# lv_io_retro.net
KiCad netlist of a schematic drawn in Altium Designer
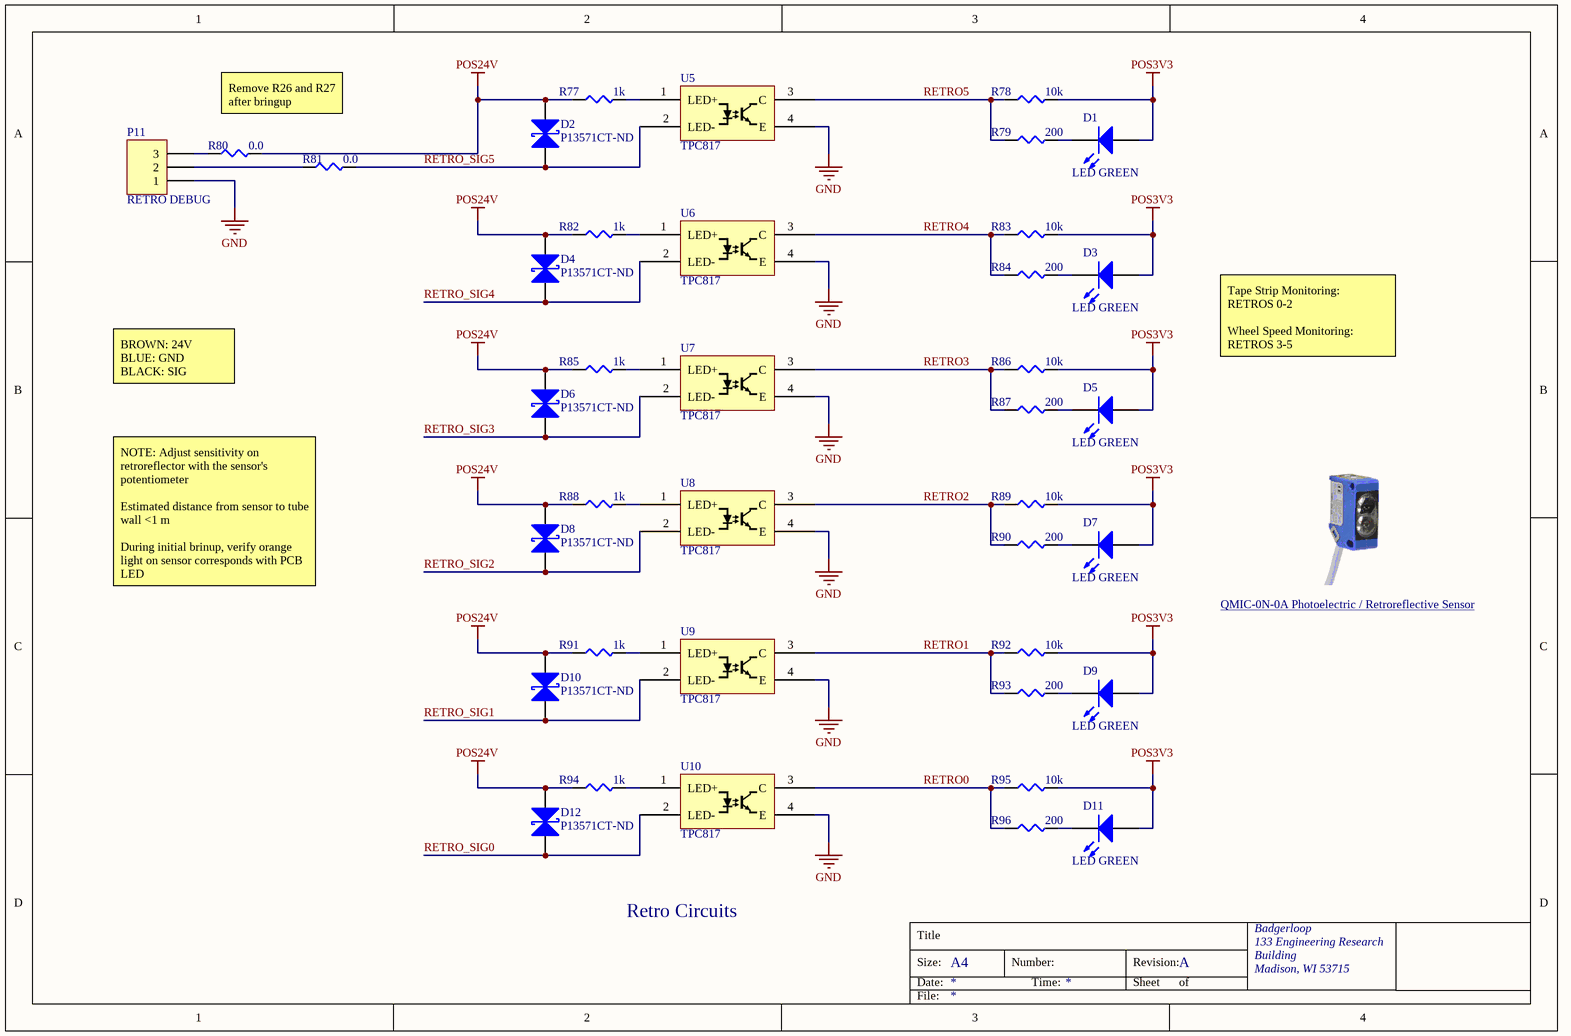
[diagram p0: lv_io_retro.SchDoc]

(export (version "E")
  (design (tool "Eeschema 10.0.6"))
  (components
    (comp (ref "D1")
      (value "LED GREEN")
      (footprint "LED 0603 GREEN")
      (fields (field (name "MANUFACTURER") "Lite-On Inc."))
      (libsource (lib "misc") (part "LED GREEN 0603"))
    )
    (comp (ref "D2")
      (value "ESD Diode")
      (footprint "SMD-0402-RES")
      (description "ESD Supressor")
      (fields (field (name "DIGIKEY P/N") "P13571CT-ND") (field (name "MANUFACTURER") "EZAEG"))
      (libsource (lib "misc") (part "ESD Diode"))
    )
    (comp (ref "D3")
      (value "LED GREEN")
      (footprint "LED 0603 GREEN")
      (fields (field (name "MANUFACTURER") "Lite-On Inc."))
      (libsource (lib "misc") (part "LED GREEN 0603"))
    )
    (comp (ref "D4")
      (value "ESD Diode")
      (footprint "SMD-0402-RES")
      (description "ESD Supressor")
      (fields (field (name "DIGIKEY P/N") "P13571CT-ND") (field (name "MANUFACTURER") "EZAEG"))
      (libsource (lib "misc") (part "ESD Diode"))
    )
    (comp (ref "D5")
      (value "LED GREEN")
      (footprint "LED 0603 GREEN")
      (fields (field (name "MANUFACTURER") "Lite-On Inc."))
      (libsource (lib "misc") (part "LED GREEN 0603"))
    )
    (comp (ref "D6")
      (value "ESD Diode")
      (footprint "SMD-0402-RES")
      (description "ESD Supressor")
      (fields (field (name "DIGIKEY P/N") "P13571CT-ND") (field (name "MANUFACTURER") "EZAEG"))
      (libsource (lib "misc") (part "ESD Diode"))
    )
    (comp (ref "D7")
      (value "LED GREEN")
      (footprint "LED 0603 GREEN")
      (fields (field (name "MANUFACTURER") "Lite-On Inc."))
      (libsource (lib "misc") (part "LED GREEN 0603"))
    )
    (comp (ref "D8")
      (value "ESD Diode")
      (footprint "SMD-0402-RES")
      (description "ESD Supressor")
      (fields (field (name "DIGIKEY P/N") "P13571CT-ND") (field (name "MANUFACTURER") "EZAEG"))
      (libsource (lib "misc") (part "ESD Diode"))
    )
    (comp (ref "D9")
      (value "LED GREEN")
      (footprint "LED 0603 GREEN")
      (fields (field (name "MANUFACTURER") "Lite-On Inc."))
      (libsource (lib "misc") (part "LED GREEN 0603"))
    )
    (comp (ref "D10")
      (value "ESD Diode")
      (footprint "SMD-0402-RES")
      (description "ESD Supressor")
      (fields (field (name "DIGIKEY P/N") "P13571CT-ND") (field (name "MANUFACTURER") "EZAEG"))
      (libsource (lib "misc") (part "ESD Diode"))
    )
    (comp (ref "D11")
      (value "LED GREEN")
      (footprint "LED 0603 GREEN")
      (fields (field (name "MANUFACTURER") "Lite-On Inc."))
      (libsource (lib "misc") (part "LED GREEN 0603"))
    )
    (comp (ref "D12")
      (value "ESD Diode")
      (footprint "SMD-0402-RES")
      (description "ESD Supressor")
      (fields (field (name "DIGIKEY P/N") "P13571CT-ND") (field (name "MANUFACTURER") "EZAEG"))
      (libsource (lib "misc") (part "ESD Diode"))
    )
    (comp (ref "P11")
      (value "RETRO DEBUG")
      (footprint "Pin Header 1x3 TH Pitch 2.54mm")
      (description "Header, 3-Pin")
      (fields (field (name "PUBLISHER") "Altium Limited"))
      (libsource (lib "connector") (part "Header 3"))
    )
    (comp (ref "R77")
      (value "1k")
      (footprint "SMD-0603-RES")
      (description "RES SMD 1K OHM 1% 1/5W 0603")
      (fields
        (field (name "PART NUMBER") "ERJ-P03F1001V")
        (field (name "DIGI-KEY PART NUMBER") "P16018CT-ND")
      )
      (libsource (lib "resistor") (part "ERJ-P03F1001V"))
    )
    (comp (ref "R78")
      (value "10k")
      (footprint "SMD-0603-RES")
      (description "RES SMD 10K OHM 5% 1/5W 0603")
      (fields (field (name "PART NUMBER") "ERJ-P03J103V") (field (name "DIGI-KEY PART NUMBER") "P16032CT-ND"))
      (libsource (lib "resistor") (part "ERJ-P03J103V"))
    )
    (comp (ref "R79")
      (value "200")
      (footprint "SMD-0603-RES")
      (description "RES SMD 200 OHM 5% 1/5W 0603")
      (fields (field (name "PART NUMBER") "ERJ-P03J201V") (field (name "DIGI-KEY PART NUMBER") "P16033CT-ND"))
      (libsource (lib "resistor") (part "ERJ-P03J201V"))
    )
    (comp (ref "R80")
      (value "0.0")
      (footprint "SMD-0402-RES")
      (description "RES SMD 0.0OHM JUMPER 1/10W 0402")
      (fields (field (name "PART NUMBER") "ERJ-2GE0R00X") (field (name "DIGI-KEY PART NUMBER") "P0.0JCT-ND"))
      (libsource (lib "resistor") (part "ERJ-2GE0R00X"))
    )
    (comp (ref "R81")
      (value "0.0")
      (footprint "SMD-0402-RES")
      (description "RES SMD 0.0OHM JUMPER 1/10W 0402")
      (fields (field (name "PART NUMBER") "ERJ-2GE0R00X") (field (name "DIGI-KEY PART NUMBER") "P0.0JCT-ND"))
      (libsource (lib "resistor") (part "ERJ-2GE0R00X"))
    )
    (comp (ref "R82")
      (value "1k")
      (footprint "SMD-0603-RES")
      (description "RES SMD 1K OHM 1% 1/5W 0603")
      (fields
        (field (name "PART NUMBER") "ERJ-P03F1001V")
        (field (name "DIGI-KEY PART NUMBER") "P16018CT-ND")
      )
      (libsource (lib "resistor") (part "ERJ-P03F1001V"))
    )
    (comp (ref "R83")
      (value "10k")
      (footprint "SMD-0603-RES")
      (description "RES SMD 10K OHM 5% 1/5W 0603")
      (fields (field (name "PART NUMBER") "ERJ-P03J103V") (field (name "DIGI-KEY PART NUMBER") "P16032CT-ND"))
      (libsource (lib "resistor") (part "ERJ-P03J103V"))
    )
    (comp (ref "R84")
      (value "200")
      (footprint "SMD-0603-RES")
      (description "RES SMD 200 OHM 5% 1/5W 0603")
      (fields (field (name "PART NUMBER") "ERJ-P03J201V") (field (name "DIGI-KEY PART NUMBER") "P16033CT-ND"))
      (libsource (lib "resistor") (part "ERJ-P03J201V"))
    )
    (comp (ref "R85")
      (value "1k")
      (footprint "SMD-0603-RES")
      (description "RES SMD 1K OHM 1% 1/5W 0603")
      (fields
        (field (name "PART NUMBER") "ERJ-P03F1001V")
        (field (name "DIGI-KEY PART NUMBER") "P16018CT-ND")
      )
      (libsource (lib "resistor") (part "ERJ-P03F1001V"))
    )
    (comp (ref "R86")
      (value "10k")
      (footprint "SMD-0603-RES")
      (description "RES SMD 10K OHM 5% 1/5W 0603")
      (fields (field (name "PART NUMBER") "ERJ-P03J103V") (field (name "DIGI-KEY PART NUMBER") "P16032CT-ND"))
      (libsource (lib "resistor") (part "ERJ-P03J103V"))
    )
    (comp (ref "R87")
      (value "200")
      (footprint "SMD-0603-RES")
      (description "RES SMD 200 OHM 5% 1/5W 0603")
      (fields (field (name "PART NUMBER") "ERJ-P03J201V") (field (name "DIGI-KEY PART NUMBER") "P16033CT-ND"))
      (libsource (lib "resistor") (part "ERJ-P03J201V"))
    )
    (comp (ref "R88")
      (value "1k")
      (footprint "SMD-0603-RES")
      (description "RES SMD 1K OHM 1% 1/5W 0603")
      (fields
        (field (name "PART NUMBER") "ERJ-P03F1001V")
        (field (name "DIGI-KEY PART NUMBER") "P16018CT-ND")
      )
      (libsource (lib "resistor") (part "ERJ-P03F1001V"))
    )
    (comp (ref "R89")
      (value "10k")
      (footprint "SMD-0603-RES")
      (description "RES SMD 10K OHM 5% 1/5W 0603")
      (fields (field (name "PART NUMBER") "ERJ-P03J103V") (field (name "DIGI-KEY PART NUMBER") "P16032CT-ND"))
      (libsource (lib "resistor") (part "ERJ-P03J103V"))
    )
    (comp (ref "R90")
      (value "200")
      (footprint "SMD-0603-RES")
      (description "RES SMD 200 OHM 5% 1/5W 0603")
      (fields (field (name "PART NUMBER") "ERJ-P03J201V") (field (name "DIGI-KEY PART NUMBER") "P16033CT-ND"))
      (libsource (lib "resistor") (part "ERJ-P03J201V"))
    )
    (comp (ref "R91")
      (value "1k")
      (footprint "SMD-0603-RES")
      (description "RES SMD 1K OHM 1% 1/5W 0603")
      (fields
        (field (name "PART NUMBER") "ERJ-P03F1001V")
        (field (name "DIGI-KEY PART NUMBER") "P16018CT-ND")
      )
      (libsource (lib "resistor") (part "ERJ-P03F1001V"))
    )
    (comp (ref "R92")
      (value "10k")
      (footprint "SMD-0603-RES")
      (description "RES SMD 10K OHM 5% 1/5W 0603")
      (fields (field (name "PART NUMBER") "ERJ-P03J103V") (field (name "DIGI-KEY PART NUMBER") "P16032CT-ND"))
      (libsource (lib "resistor") (part "ERJ-P03J103V"))
    )
    (comp (ref "R93")
      (value "200")
      (footprint "SMD-0603-RES")
      (description "RES SMD 200 OHM 5% 1/5W 0603")
      (fields (field (name "PART NUMBER") "ERJ-P03J201V") (field (name "DIGI-KEY PART NUMBER") "P16033CT-ND"))
      (libsource (lib "resistor") (part "ERJ-P03J201V"))
    )
    (comp (ref "R94")
      (value "1k")
      (footprint "SMD-0603-RES")
      (description "RES SMD 1K OHM 1% 1/5W 0603")
      (fields
        (field (name "PART NUMBER") "ERJ-P03F1001V")
        (field (name "DIGI-KEY PART NUMBER") "P16018CT-ND")
      )
      (libsource (lib "resistor") (part "ERJ-P03F1001V"))
    )
    (comp (ref "R95")
      (value "10k")
      (footprint "SMD-0603-RES")
      (description "RES SMD 10K OHM 5% 1/5W 0603")
      (fields (field (name "PART NUMBER") "ERJ-P03J103V") (field (name "DIGI-KEY PART NUMBER") "P16032CT-ND"))
      (libsource (lib "resistor") (part "ERJ-P03J103V"))
    )
    (comp (ref "R96")
      (value "200")
      (footprint "SMD-0603-RES")
      (description "RES SMD 200 OHM 5% 1/5W 0603")
      (fields (field (name "PART NUMBER") "ERJ-P03J201V") (field (name "DIGI-KEY PART NUMBER") "P16033CT-ND"))
      (libsource (lib "resistor") (part "ERJ-P03J201V"))
    )
    (comp (ref "U5")
      (value "TPC817")
      (footprint "SOT200P1005X328-5N")
      (description "OPTOISO 5KV TRANS 4SOP")
      (fields (field (name "MANUFACTURER") "Taiwan Semi"))
      (libsource (lib "ic") (part "TPC817"))
    )
    (comp (ref "U6")
      (value "TPC817")
      (footprint "SOT200P1005X328-5N")
      (description "OPTOISO 5KV TRANS 4SOP")
      (fields (field (name "MANUFACTURER") "Taiwan Semi"))
      (libsource (lib "ic") (part "TPC817"))
    )
    (comp (ref "U7")
      (value "TPC817")
      (footprint "SOT200P1005X328-5N")
      (description "OPTOISO 5KV TRANS 4SOP")
      (fields (field (name "MANUFACTURER") "Taiwan Semi"))
      (libsource (lib "ic") (part "TPC817"))
    )
    (comp (ref "U8")
      (value "TPC817")
      (footprint "SOT200P1005X328-5N")
      (description "OPTOISO 5KV TRANS 4SOP")
      (fields (field (name "MANUFACTURER") "Taiwan Semi"))
      (libsource (lib "ic") (part "TPC817"))
    )
    (comp (ref "U9")
      (value "TPC817")
      (footprint "SOT200P1005X328-5N")
      (description "OPTOISO 5KV TRANS 4SOP")
      (fields (field (name "MANUFACTURER") "Taiwan Semi"))
      (libsource (lib "ic") (part "TPC817"))
    )
    (comp (ref "U10")
      (value "TPC817")
      (footprint "SOT200P1005X328-5N")
      (description "OPTOISO 5KV TRANS 4SOP")
      (fields (field (name "MANUFACTURER") "Taiwan Semi"))
      (libsource (lib "ic") (part "TPC817"))
    )
  )
  (nets
    (net (code "1") (name "/RETRO0") (class "Default")
      (node (ref "R95") (pin "1") (pinfunction "1_1") (pintype "passive"))
      (node (ref "R96") (pin "1") (pinfunction "1_1") (pintype "passive"))
      (node (ref "U10") (pin "3") (pinfunction "C_3") (pintype "passive"))
    )
    (net (code "2") (name "/RETRO1") (class "Default")
      (node (ref "R92") (pin "1") (pinfunction "1_1") (pintype "passive"))
      (node (ref "R93") (pin "1") (pinfunction "1_1") (pintype "passive"))
      (node (ref "U9") (pin "3") (pinfunction "C_3") (pintype "passive"))
    )
    (net (code "3") (name "/RETRO2") (class "Default")
      (node (ref "R89") (pin "1") (pinfunction "1_1") (pintype "passive"))
      (node (ref "R90") (pin "1") (pinfunction "1_1") (pintype "passive"))
      (node (ref "U8") (pin "3") (pinfunction "C_3") (pintype "passive"))
    )
    (net (code "4") (name "/RETRO3") (class "Default")
      (node (ref "R86") (pin "1") (pinfunction "1_1") (pintype "passive"))
      (node (ref "R87") (pin "1") (pinfunction "1_1") (pintype "passive"))
      (node (ref "U7") (pin "3") (pinfunction "C_3") (pintype "passive"))
    )
    (net (code "5") (name "/RETRO4") (class "Default")
      (node (ref "R83") (pin "1") (pinfunction "1_1") (pintype "passive"))
      (node (ref "R84") (pin "1") (pinfunction "1_1") (pintype "passive"))
      (node (ref "U6") (pin "3") (pinfunction "C_3") (pintype "passive"))
    )
    (net (code "6") (name "/RETRO5") (class "Default")
      (node (ref "R78") (pin "1") (pinfunction "1_1") (pintype "passive"))
      (node (ref "R79") (pin "1") (pinfunction "1_1") (pintype "passive"))
      (node (ref "U5") (pin "3") (pinfunction "C_3") (pintype "passive"))
    )
    (net (code "7") (name "/RETRO_SIG0") (class "Default")
      (node (ref "D12") (pin "1") (pinfunction "A_1") (pintype "passive"))
      (node (ref "U10") (pin "2") (pinfunction "LED-_2") (pintype "passive"))
    )
    (net (code "8") (name "/RETRO_SIG1") (class "Default")
      (node (ref "D10") (pin "1") (pinfunction "A_1") (pintype "passive"))
      (node (ref "U9") (pin "2") (pinfunction "LED-_2") (pintype "passive"))
    )
    (net (code "9") (name "/RETRO_SIG2") (class "Default")
      (node (ref "D8") (pin "1") (pinfunction "A_1") (pintype "passive"))
      (node (ref "U8") (pin "2") (pinfunction "LED-_2") (pintype "passive"))
    )
    (net (code "10") (name "/RETRO_SIG3") (class "Default")
      (node (ref "D6") (pin "1") (pinfunction "A_1") (pintype "passive"))
      (node (ref "U7") (pin "2") (pinfunction "LED-_2") (pintype "passive"))
    )
    (net (code "11") (name "/RETRO_SIG4") (class "Default")
      (node (ref "D4") (pin "1") (pinfunction "A_1") (pintype "passive"))
      (node (ref "U6") (pin "2") (pinfunction "LED-_2") (pintype "passive"))
    )
    (net (code "12") (name "/RETRO_SIG5") (class "Default")
      (node (ref "D2") (pin "1") (pinfunction "A_1") (pintype "passive"))
      (node (ref "R81") (pin "2") (pinfunction "2_2") (pintype "passive"))
      (node (ref "U5") (pin "2") (pinfunction "LED-_2") (pintype "passive"))
    )
    (net (code "13") (name "GND") (class "Default")
      (node (ref "P11") (pin "1") (pinfunction "1_1") (pintype "passive"))
      (node (ref "U10") (pin "4") (pinfunction "E_4") (pintype "passive"))
      (node (ref "U5") (pin "4") (pinfunction "E_4") (pintype "passive"))
      (node (ref "U6") (pin "4") (pinfunction "E_4") (pintype "passive"))
      (node (ref "U7") (pin "4") (pinfunction "E_4") (pintype "passive"))
      (node (ref "U8") (pin "4") (pinfunction "E_4") (pintype "passive"))
      (node (ref "U9") (pin "4") (pinfunction "E_4") (pintype "passive"))
    )
    (net (code "14") (name "Net-(D1-K)") (class "Default")
      (node (ref "D1") (pin "2") (pinfunction "K_2") (pintype "passive"))
      (node (ref "R79") (pin "2") (pinfunction "2_2") (pintype "passive"))
    )
    (net (code "15") (name "Net-(D3-K)") (class "Default")
      (node (ref "D3") (pin "2") (pinfunction "K_2") (pintype "passive"))
      (node (ref "R84") (pin "2") (pinfunction "2_2") (pintype "passive"))
    )
    (net (code "16") (name "Net-(D5-K)") (class "Default")
      (node (ref "D5") (pin "2") (pinfunction "K_2") (pintype "passive"))
      (node (ref "R87") (pin "2") (pinfunction "2_2") (pintype "passive"))
    )
    (net (code "17") (name "Net-(D7-K)") (class "Default")
      (node (ref "D7") (pin "2") (pinfunction "K_2") (pintype "passive"))
      (node (ref "R90") (pin "2") (pinfunction "2_2") (pintype "passive"))
    )
    (net (code "18") (name "Net-(D9-K)") (class "Default")
      (node (ref "D9") (pin "2") (pinfunction "K_2") (pintype "passive"))
      (node (ref "R93") (pin "2") (pinfunction "2_2") (pintype "passive"))
    )
    (net (code "19") (name "Net-(D11-K)") (class "Default")
      (node (ref "D11") (pin "2") (pinfunction "K_2") (pintype "passive"))
      (node (ref "R96") (pin "2") (pinfunction "2_2") (pintype "passive"))
    )
    (net (code "20") (name "Net-(P11-Pad2)") (class "Default")
      (node (ref "P11") (pin "2") (pinfunction "2_2") (pintype "passive"))
      (node (ref "R81") (pin "1") (pinfunction "1_1") (pintype "passive"))
    )
    (net (code "21") (name "Net-(P11-Pad3)") (class "Default")
      (node (ref "P11") (pin "3") (pinfunction "3_3") (pintype "passive"))
      (node (ref "R80") (pin "1") (pinfunction "1_1") (pintype "passive"))
    )
    (net (code "22") (name "Net-(U5-LED+)") (class "Default")
      (node (ref "R77") (pin "2") (pinfunction "2_2") (pintype "passive"))
      (node (ref "U5") (pin "1") (pinfunction "LED+_1") (pintype "passive"))
    )
    (net (code "23") (name "Net-(U6-LED+)") (class "Default")
      (node (ref "R82") (pin "2") (pinfunction "2_2") (pintype "passive"))
      (node (ref "U6") (pin "1") (pinfunction "LED+_1") (pintype "passive"))
    )
    (net (code "24") (name "Net-(U7-LED+)") (class "Default")
      (node (ref "R85") (pin "2") (pinfunction "2_2") (pintype "passive"))
      (node (ref "U7") (pin "1") (pinfunction "LED+_1") (pintype "passive"))
    )
    (net (code "25") (name "Net-(U8-LED+)") (class "Default")
      (node (ref "R88") (pin "2") (pinfunction "2_2") (pintype "passive"))
      (node (ref "U8") (pin "1") (pinfunction "LED+_1") (pintype "passive"))
    )
    (net (code "26") (name "Net-(U9-LED+)") (class "Default")
      (node (ref "R91") (pin "2") (pinfunction "2_2") (pintype "passive"))
      (node (ref "U9") (pin "1") (pinfunction "LED+_1") (pintype "passive"))
    )
    (net (code "27") (name "Net-(U10-LED+)") (class "Default")
      (node (ref "R94") (pin "2") (pinfunction "2_2") (pintype "passive"))
      (node (ref "U10") (pin "1") (pinfunction "LED+_1") (pintype "passive"))
    )
    (net (code "28") (name "POS3V3") (class "Default")
      (node (ref "D1") (pin "1") (pinfunction "A_1") (pintype "passive"))
      (node (ref "D11") (pin "1") (pinfunction "A_1") (pintype "passive"))
      (node (ref "D3") (pin "1") (pinfunction "A_1") (pintype "passive"))
      (node (ref "D5") (pin "1") (pinfunction "A_1") (pintype "passive"))
      (node (ref "D7") (pin "1") (pinfunction "A_1") (pintype "passive"))
      (node (ref "D9") (pin "1") (pinfunction "A_1") (pintype "passive"))
      (node (ref "R78") (pin "2") (pinfunction "2_2") (pintype "passive"))
      (node (ref "R83") (pin "2") (pinfunction "2_2") (pintype "passive"))
      (node (ref "R86") (pin "2") (pinfunction "2_2") (pintype "passive"))
      (node (ref "R89") (pin "2") (pinfunction "2_2") (pintype "passive"))
      (node (ref "R92") (pin "2") (pinfunction "2_2") (pintype "passive"))
      (node (ref "R95") (pin "2") (pinfunction "2_2") (pintype "passive"))
    )
    (net (code "29") (name "POS24V") (class "Default")
      (node (ref "D10") (pin "2") (pinfunction "K_2") (pintype "passive"))
      (node (ref "D12") (pin "2") (pinfunction "K_2") (pintype "passive"))
      (node (ref "D2") (pin "2") (pinfunction "K_2") (pintype "passive"))
      (node (ref "D4") (pin "2") (pinfunction "K_2") (pintype "passive"))
      (node (ref "D6") (pin "2") (pinfunction "K_2") (pintype "passive"))
      (node (ref "D8") (pin "2") (pinfunction "K_2") (pintype "passive"))
      (node (ref "R77") (pin "1") (pinfunction "1_1") (pintype "passive"))
      (node (ref "R80") (pin "2") (pinfunction "2_2") (pintype "passive"))
      (node (ref "R82") (pin "1") (pinfunction "1_1") (pintype "passive"))
      (node (ref "R85") (pin "1") (pinfunction "1_1") (pintype "passive"))
      (node (ref "R88") (pin "1") (pinfunction "1_1") (pintype "passive"))
      (node (ref "R91") (pin "1") (pinfunction "1_1") (pintype "passive"))
      (node (ref "R94") (pin "1") (pinfunction "1_1") (pintype "passive"))
    )
  )
)
